# ALIMENTATION.net
KiCad netlist of a schematic drawn in EAGLE
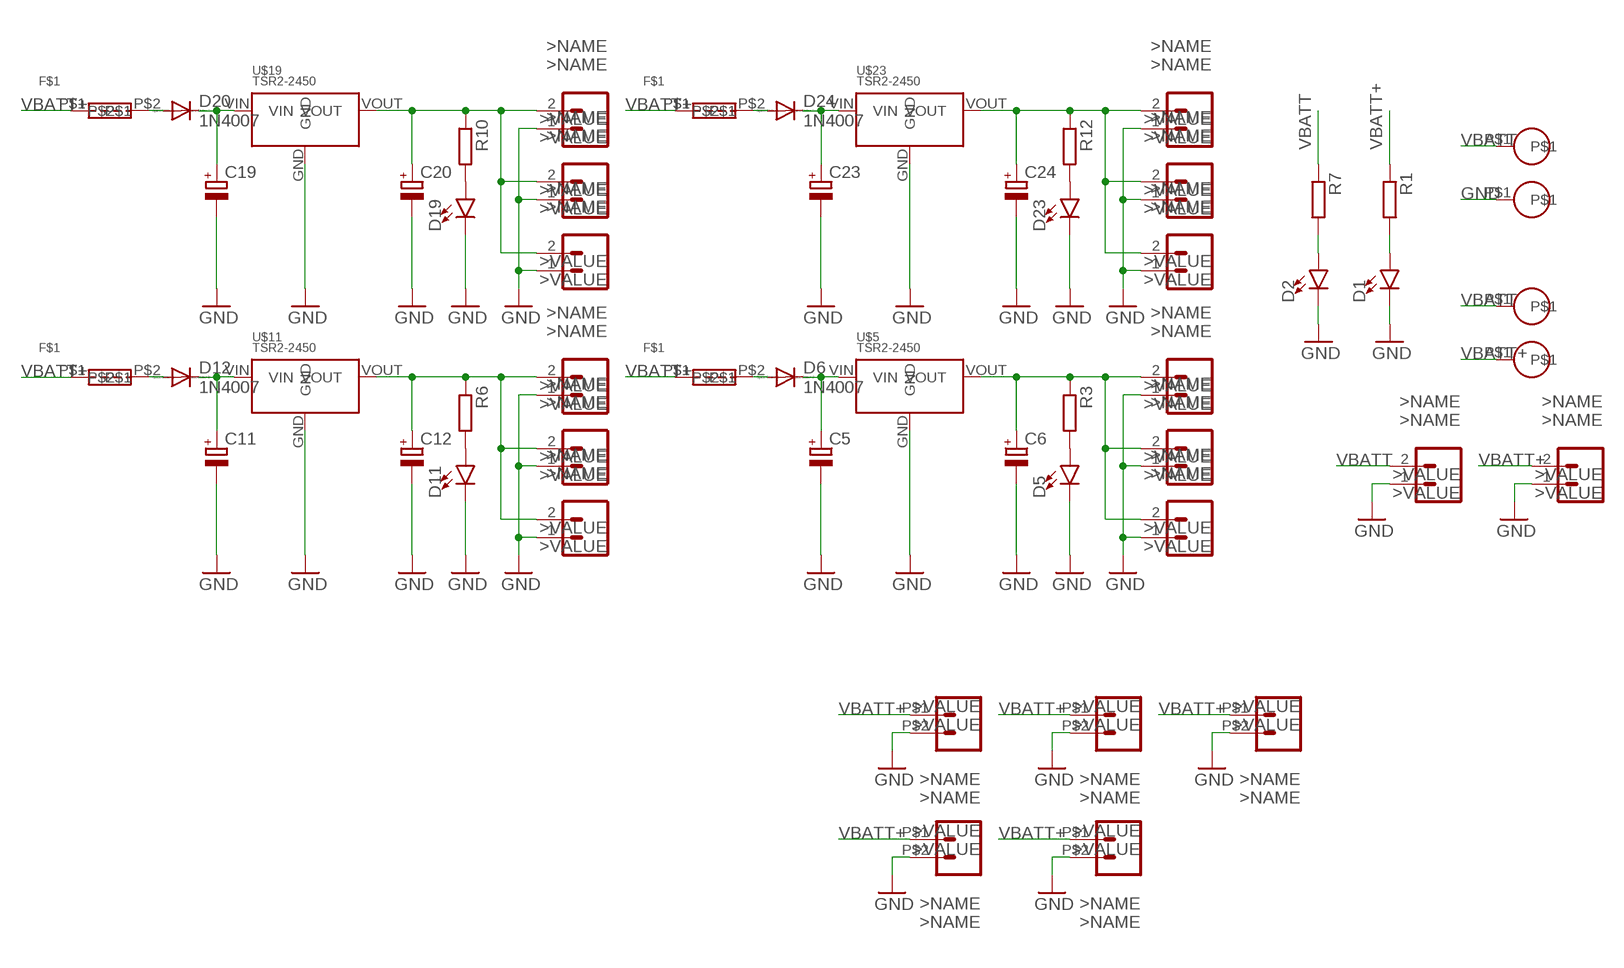
[diagram p0: schematic, sheet 1]

(export (version "E")
  (design (tool "Eeschema 10.0.6"))
  (components
    (comp (ref "C5")
      (value "CPOL-EUE2-5")
      (footprint "eagle-import:E2-5")
      (libsource (lib "eagle-import") (part "CPOL-EUE2-5"))
    )
    (comp (ref "C6")
      (value "CPOL-EUE2-5")
      (footprint "eagle-import:E2-5")
      (libsource (lib "eagle-import") (part "CPOL-EUE2-5"))
    )
    (comp (ref "C11")
      (value "CPOL-EUE2-5")
      (footprint "eagle-import:E2-5")
      (libsource (lib "eagle-import") (part "CPOL-EUE2-5"))
    )
    (comp (ref "C12")
      (value "CPOL-EUE2-5")
      (footprint "eagle-import:E2-5")
      (libsource (lib "eagle-import") (part "CPOL-EUE2-5"))
    )
    (comp (ref "C19")
      (value "CPOL-EUE2-5")
      (footprint "eagle-import:E2-5")
      (libsource (lib "eagle-import") (part "CPOL-EUE2-5"))
    )
    (comp (ref "C20")
      (value "CPOL-EUE2-5")
      (footprint "eagle-import:E2-5")
      (libsource (lib "eagle-import") (part "CPOL-EUE2-5"))
    )
    (comp (ref "C23")
      (value "CPOL-EUE2-5")
      (footprint "eagle-import:E2-5")
      (libsource (lib "eagle-import") (part "CPOL-EUE2-5"))
    )
    (comp (ref "C24")
      (value "CPOL-EUE2-5")
      (footprint "eagle-import:E2-5")
      (libsource (lib "eagle-import") (part "CPOL-EUE2-5"))
    )
    (comp (ref "D1")
      (value "LED3MM")
      (footprint "eagle-import:LED_3MM")
      (libsource (lib "eagle-import") (part "LED3MM"))
    )
    (comp (ref "D2")
      (value "LED3MM")
      (footprint "eagle-import:LED_3MM")
      (libsource (lib "eagle-import") (part "LED3MM"))
    )
    (comp (ref "D5")
      (value "LED3MM")
      (footprint "eagle-import:LED_3MM")
      (libsource (lib "eagle-import") (part "LED3MM"))
    )
    (comp (ref "D6")
      (value "1N4007")
      (footprint "eagle-import:DO41-10")
      (libsource (lib "eagle-import") (part "1N4004"))
    )
    (comp (ref "D11")
      (value "LED3MM")
      (footprint "eagle-import:LED_3MM")
      (libsource (lib "eagle-import") (part "LED3MM"))
    )
    (comp (ref "D12")
      (value "1N4007")
      (footprint "eagle-import:DO41-10")
      (libsource (lib "eagle-import") (part "1N4004"))
    )
    (comp (ref "D19")
      (value "LED3MM")
      (footprint "eagle-import:LED_3MM")
      (libsource (lib "eagle-import") (part "LED3MM"))
    )
    (comp (ref "D20")
      (value "1N4007")
      (footprint "eagle-import:DO41-10")
      (libsource (lib "eagle-import") (part "1N4004"))
    )
    (comp (ref "D23")
      (value "LED3MM")
      (footprint "eagle-import:LED_3MM")
      (libsource (lib "eagle-import") (part "LED3MM"))
    )
    (comp (ref "D24")
      (value "1N4007")
      (footprint "eagle-import:DO41-10")
      (libsource (lib "eagle-import") (part "1N4004"))
    )
    (comp (ref "J1")
      (value "CONN_02POLAR")
      (footprint "eagle-import:MOLEX-1X2")
      (libsource (lib "eagle-import") (part "CONN_02POLAR"))
    )
    (comp (ref "J2")
      (value "CONN_02POLAR")
      (footprint "eagle-import:MOLEX-1X2")
      (libsource (lib "eagle-import") (part "CONN_02POLAR"))
    )
    (comp (ref "J3")
      (value "CONN_027A-C")
      (footprint "eagle-import:NSK396-2C")
      (libsource (lib "eagle-import") (part "CONN_027A-C"))
    )
    (comp (ref "J7")
      (value "CONN_02POLAR")
      (footprint "eagle-import:MOLEX-1X2")
      (libsource (lib "eagle-import") (part "CONN_02POLAR"))
    )
    (comp (ref "J8")
      (value "CONN_02POLAR")
      (footprint "eagle-import:MOLEX-1X2")
      (libsource (lib "eagle-import") (part "CONN_02POLAR"))
    )
    (comp (ref "J9")
      (value "CONN_02POLAR")
      (footprint "eagle-import:MOLEX-1X2")
      (libsource (lib "eagle-import") (part "CONN_02POLAR"))
    )
    (comp (ref "J10")
      (value "CONN_027A-C")
      (footprint "eagle-import:NSK396-2C")
      (libsource (lib "eagle-import") (part "CONN_027A-C"))
    )
    (comp (ref "J11")
      (value "CONN_027A-C")
      (footprint "eagle-import:NSK396-2C")
      (libsource (lib "eagle-import") (part "CONN_027A-C"))
    )
    (comp (ref "J12")
      (value "CONN_027A-C")
      (footprint "eagle-import:NSK396-2C")
      (libsource (lib "eagle-import") (part "CONN_027A-C"))
    )
    (comp (ref "J13")
      (value "CONN_027A-C")
      (footprint "eagle-import:NSK396-2C")
      (libsource (lib "eagle-import") (part "CONN_027A-C"))
    )
    (comp (ref "J16")
      (value "CONN_02POLAR")
      (footprint "eagle-import:MOLEX-1X2")
      (libsource (lib "eagle-import") (part "CONN_02POLAR"))
    )
    (comp (ref "J17")
      (value "CONN_02POLAR")
      (footprint "eagle-import:MOLEX-1X2")
      (libsource (lib "eagle-import") (part "CONN_02POLAR"))
    )
    (comp (ref "J18")
      (value "CONN_02POLAR")
      (footprint "eagle-import:MOLEX-1X2")
      (libsource (lib "eagle-import") (part "CONN_02POLAR"))
    )
    (comp (ref "J28")
      (value "CONN_02POLAR")
      (footprint "eagle-import:MOLEX-1X2")
      (libsource (lib "eagle-import") (part "CONN_02POLAR"))
    )
    (comp (ref "J29")
      (value "CONN_02POLAR")
      (footprint "eagle-import:MOLEX-1X2")
      (libsource (lib "eagle-import") (part "CONN_02POLAR"))
    )
    (comp (ref "J30")
      (value "CONN_02POLAR")
      (footprint "eagle-import:MOLEX-1X2")
      (libsource (lib "eagle-import") (part "CONN_02POLAR"))
    )
    (comp (ref "J34")
      (value "CONN_02POLAR")
      (footprint "eagle-import:MOLEX-1X2")
      (libsource (lib "eagle-import") (part "CONN_02POLAR"))
    )
    (comp (ref "J35")
      (value "CONN_02POLAR")
      (footprint "eagle-import:MOLEX-1X2")
      (libsource (lib "eagle-import") (part "CONN_02POLAR"))
    )
    (comp (ref "J36")
      (value "CONN_02POLAR")
      (footprint "eagle-import:MOLEX-1X2")
      (libsource (lib "eagle-import") (part "CONN_02POLAR"))
    )
    (comp (ref "R1")
      (value "R-EU_0204/2V")
      (footprint "eagle-import:0204V")
      (libsource (lib "eagle-import") (part "R-EU_0204/2V"))
    )
    (comp (ref "R3")
      (value "R-EU_0204/2V")
      (footprint "eagle-import:0204V")
      (libsource (lib "eagle-import") (part "R-EU_0204/2V"))
    )
    (comp (ref "R6")
      (value "R-EU_0204/2V")
      (footprint "eagle-import:0204V")
      (libsource (lib "eagle-import") (part "R-EU_0204/2V"))
    )
    (comp (ref "R7")
      (value "R-EU_0204/2V")
      (footprint "eagle-import:0204V")
      (libsource (lib "eagle-import") (part "R-EU_0204/2V"))
    )
    (comp (ref "R10")
      (value "R-EU_0204/2V")
      (footprint "eagle-import:0204V")
      (libsource (lib "eagle-import") (part "R-EU_0204/2V"))
    )
    (comp (ref "R12")
      (value "R-EU_0204/2V")
      (footprint "eagle-import:0204V")
      (libsource (lib "eagle-import") (part "R-EU_0204/2V"))
    )
    (comp (ref "U$1")
      (value "BATTERY_PAD")
      (footprint "eagle-import:BATTERY_PAD")
      (libsource (lib "eagle-import") (part "BATTERY_PAD"))
    )
    (comp (ref "U$2")
      (value "BATTERY_PAD")
      (footprint "eagle-import:BATTERY_PAD")
      (libsource (lib "eagle-import") (part "BATTERY_PAD"))
    )
    (comp (ref "U$5")
      (value "TSR2-2450")
      (footprint "eagle-import:TSR2-2450")
      (libsource (lib "eagle-import") (part "TSR2-2450"))
    )
    (comp (ref "U$6")
      (value "RUEF_POLY")
      (footprint "eagle-import:RUEF185")
      (libsource (lib "eagle-import") (part "RUEF_POLY"))
    )
    (comp (ref "U$11")
      (value "TSR2-2450")
      (footprint "eagle-import:TSR2-2450")
      (libsource (lib "eagle-import") (part "TSR2-2450"))
    )
    (comp (ref "U$12")
      (value "RUEF_POLY")
      (footprint "eagle-import:RUEF185")
      (libsource (lib "eagle-import") (part "RUEF_POLY"))
    )
    (comp (ref "U$13")
      (value "BATTERY_PAD")
      (footprint "eagle-import:BATTERY_PAD")
      (libsource (lib "eagle-import") (part "BATTERY_PAD"))
    )
    (comp (ref "U$14")
      (value "BATTERY_PAD")
      (footprint "eagle-import:BATTERY_PAD")
      (libsource (lib "eagle-import") (part "BATTERY_PAD"))
    )
    (comp (ref "U$19")
      (value "TSR2-2450")
      (footprint "eagle-import:TSR2-2450")
      (libsource (lib "eagle-import") (part "TSR2-2450"))
    )
    (comp (ref "U$20")
      (value "RUEF_POLY")
      (footprint "eagle-import:RUEF185")
      (libsource (lib "eagle-import") (part "RUEF_POLY"))
    )
    (comp (ref "U$23")
      (value "TSR2-2450")
      (footprint "eagle-import:TSR2-2450")
      (libsource (lib "eagle-import") (part "TSR2-2450"))
    )
    (comp (ref "U$24")
      (value "RUEF_POLY")
      (footprint "eagle-import:RUEF185")
      (libsource (lib "eagle-import") (part "RUEF_POLY"))
    )
  )
  (nets
    (net (code "1") (name "/VBATT") (class "Default")
      (node (ref "J1") (pin "2") (pinfunction "2_2") (pintype "passive"))
      (node (ref "R7") (pin "1") (pinfunction "1_1") (pintype "passive"))
      (node (ref "U$1") (pin "P$1") (pinfunction "P$1_P$1") (pintype "bidirectional"))
      (node (ref "U$13") (pin "P$1") (pinfunction "P$1_P$1") (pintype "bidirectional"))
    )
    (net (code "2") (name "/VBATT+") (class "Default")
      (node (ref "J10") (pin "P$1") (pinfunction "1_P$1") (pintype "passive"))
      (node (ref "J11") (pin "P$1") (pinfunction "1_P$1") (pintype "passive"))
      (node (ref "J12") (pin "P$1") (pinfunction "1_P$1") (pintype "passive"))
      (node (ref "J13") (pin "P$1") (pinfunction "1_P$1") (pintype "passive"))
      (node (ref "J2") (pin "2") (pinfunction "2_2") (pintype "passive"))
      (node (ref "J3") (pin "P$1") (pinfunction "1_P$1") (pintype "passive"))
      (node (ref "R1") (pin "1") (pinfunction "1_1") (pintype "passive"))
      (node (ref "U$12") (pin "P$1") (pinfunction "P$1_P$1") (pintype "bidirectional"))
      (node (ref "U$14") (pin "P$1") (pinfunction "P$1_P$1") (pintype "bidirectional"))
      (node (ref "U$20") (pin "P$1") (pinfunction "P$1_P$1") (pintype "bidirectional"))
      (node (ref "U$24") (pin "P$1") (pinfunction "P$1_P$1") (pintype "bidirectional"))
      (node (ref "U$6") (pin "P$1") (pinfunction "P$1_P$1") (pintype "bidirectional"))
    )
    (net (code "3") (name "GND") (class "Default")
      (node (ref "C11") (pin "-") (pinfunction "-_-") (pintype "passive"))
      (node (ref "C12") (pin "-") (pinfunction "-_-") (pintype "passive"))
      (node (ref "C19") (pin "-") (pinfunction "-_-") (pintype "passive"))
      (node (ref "C20") (pin "-") (pinfunction "-_-") (pintype "passive"))
      (node (ref "C23") (pin "-") (pinfunction "-_-") (pintype "passive"))
      (node (ref "C24") (pin "-") (pinfunction "-_-") (pintype "passive"))
      (node (ref "C5") (pin "-") (pinfunction "-_-") (pintype "passive"))
      (node (ref "C6") (pin "-") (pinfunction "-_-") (pintype "passive"))
      (node (ref "D1") (pin "K") (pinfunction "C_K") (pintype "passive"))
      (node (ref "D11") (pin "K") (pinfunction "C_K") (pintype "passive"))
      (node (ref "D19") (pin "K") (pinfunction "C_K") (pintype "passive"))
      (node (ref "D2") (pin "K") (pinfunction "C_K") (pintype "passive"))
      (node (ref "D23") (pin "K") (pinfunction "C_K") (pintype "passive"))
      (node (ref "D5") (pin "K") (pinfunction "C_K") (pintype "passive"))
      (node (ref "J1") (pin "1") (pinfunction "1_1") (pintype "passive"))
      (node (ref "J10") (pin "P$2") (pinfunction "2_P$2") (pintype "passive"))
      (node (ref "J11") (pin "P$2") (pinfunction "2_P$2") (pintype "passive"))
      (node (ref "J12") (pin "P$2") (pinfunction "2_P$2") (pintype "passive"))
      (node (ref "J13") (pin "P$2") (pinfunction "2_P$2") (pintype "passive"))
      (node (ref "J16") (pin "1") (pinfunction "1_1") (pintype "passive"))
      (node (ref "J17") (pin "1") (pinfunction "1_1") (pintype "passive"))
      (node (ref "J18") (pin "1") (pinfunction "1_1") (pintype "passive"))
      (node (ref "J2") (pin "1") (pinfunction "1_1") (pintype "passive"))
      (node (ref "J28") (pin "1") (pinfunction "1_1") (pintype "passive"))
      (node (ref "J29") (pin "1") (pinfunction "1_1") (pintype "passive"))
      (node (ref "J3") (pin "P$2") (pinfunction "2_P$2") (pintype "passive"))
      (node (ref "J30") (pin "1") (pinfunction "1_1") (pintype "passive"))
      (node (ref "J34") (pin "1") (pinfunction "1_1") (pintype "passive"))
      (node (ref "J35") (pin "1") (pinfunction "1_1") (pintype "passive"))
      (node (ref "J36") (pin "1") (pinfunction "1_1") (pintype "passive"))
      (node (ref "J7") (pin "1") (pinfunction "1_1") (pintype "passive"))
      (node (ref "J8") (pin "1") (pinfunction "1_1") (pintype "passive"))
      (node (ref "J9") (pin "1") (pinfunction "1_1") (pintype "passive"))
      (node (ref "U$11") (pin "GND") (pinfunction "GND_GND") (pintype "bidirectional"))
      (node (ref "U$19") (pin "GND") (pinfunction "GND_GND") (pintype "bidirectional"))
      (node (ref "U$2") (pin "P$1") (pinfunction "P$1_P$1") (pintype "bidirectional"))
      (node (ref "U$23") (pin "GND") (pinfunction "GND_GND") (pintype "bidirectional"))
      (node (ref "U$5") (pin "GND") (pinfunction "GND_GND") (pintype "bidirectional"))
    )
    (net (code "4") (name "Net-(C5-Pad+)") (class "Default")
      (node (ref "C5") (pin "+") (pinfunction "+_+") (pintype "passive"))
      (node (ref "D6") (pin "C") (pinfunction "C_C") (pintype "passive"))
      (node (ref "U$5") (pin "VIN") (pinfunction "VIN_VIN") (pintype "bidirectional"))
    )
    (net (code "5") (name "Net-(C6-Pad+)") (class "Default")
      (node (ref "C6") (pin "+") (pinfunction "+_+") (pintype "passive"))
      (node (ref "J7") (pin "2") (pinfunction "2_2") (pintype "passive"))
      (node (ref "J8") (pin "2") (pinfunction "2_2") (pintype "passive"))
      (node (ref "J9") (pin "2") (pinfunction "2_2") (pintype "passive"))
      (node (ref "R3") (pin "1") (pinfunction "1_1") (pintype "passive"))
      (node (ref "U$5") (pin "VOUT") (pinfunction "VOUT_VOUT") (pintype "bidirectional"))
    )
    (net (code "6") (name "Net-(C11-Pad+)") (class "Default")
      (node (ref "C11") (pin "+") (pinfunction "+_+") (pintype "passive"))
      (node (ref "D12") (pin "C") (pinfunction "C_C") (pintype "passive"))
      (node (ref "U$11") (pin "VIN") (pinfunction "VIN_VIN") (pintype "bidirectional"))
    )
    (net (code "7") (name "Net-(C12-Pad+)") (class "Default")
      (node (ref "C12") (pin "+") (pinfunction "+_+") (pintype "passive"))
      (node (ref "J16") (pin "2") (pinfunction "2_2") (pintype "passive"))
      (node (ref "J17") (pin "2") (pinfunction "2_2") (pintype "passive"))
      (node (ref "J18") (pin "2") (pinfunction "2_2") (pintype "passive"))
      (node (ref "R6") (pin "1") (pinfunction "1_1") (pintype "passive"))
      (node (ref "U$11") (pin "VOUT") (pinfunction "VOUT_VOUT") (pintype "bidirectional"))
    )
    (net (code "8") (name "Net-(C19-Pad+)") (class "Default")
      (node (ref "C19") (pin "+") (pinfunction "+_+") (pintype "passive"))
      (node (ref "D20") (pin "C") (pinfunction "C_C") (pintype "passive"))
      (node (ref "U$19") (pin "VIN") (pinfunction "VIN_VIN") (pintype "bidirectional"))
    )
    (net (code "9") (name "Net-(C20-Pad+)") (class "Default")
      (node (ref "C20") (pin "+") (pinfunction "+_+") (pintype "passive"))
      (node (ref "J28") (pin "2") (pinfunction "2_2") (pintype "passive"))
      (node (ref "J29") (pin "2") (pinfunction "2_2") (pintype "passive"))
      (node (ref "J30") (pin "2") (pinfunction "2_2") (pintype "passive"))
      (node (ref "R10") (pin "1") (pinfunction "1_1") (pintype "passive"))
      (node (ref "U$19") (pin "VOUT") (pinfunction "VOUT_VOUT") (pintype "bidirectional"))
    )
    (net (code "10") (name "Net-(C23-Pad+)") (class "Default")
      (node (ref "C23") (pin "+") (pinfunction "+_+") (pintype "passive"))
      (node (ref "D24") (pin "C") (pinfunction "C_C") (pintype "passive"))
      (node (ref "U$23") (pin "VIN") (pinfunction "VIN_VIN") (pintype "bidirectional"))
    )
    (net (code "11") (name "Net-(C24-Pad+)") (class "Default")
      (node (ref "C24") (pin "+") (pinfunction "+_+") (pintype "passive"))
      (node (ref "J34") (pin "2") (pinfunction "2_2") (pintype "passive"))
      (node (ref "J35") (pin "2") (pinfunction "2_2") (pintype "passive"))
      (node (ref "J36") (pin "2") (pinfunction "2_2") (pintype "passive"))
      (node (ref "R12") (pin "1") (pinfunction "1_1") (pintype "passive"))
      (node (ref "U$23") (pin "VOUT") (pinfunction "VOUT_VOUT") (pintype "bidirectional"))
    )
    (net (code "12") (name "Net-(D1-PadA)") (class "Default")
      (node (ref "D1") (pin "A") (pinfunction "A_A") (pintype "passive"))
      (node (ref "R1") (pin "2") (pinfunction "2_2") (pintype "passive"))
    )
    (net (code "13") (name "Net-(D2-PadA)") (class "Default")
      (node (ref "D2") (pin "A") (pinfunction "A_A") (pintype "passive"))
      (node (ref "R7") (pin "2") (pinfunction "2_2") (pintype "passive"))
    )
    (net (code "14") (name "Net-(D5-PadA)") (class "Default")
      (node (ref "D5") (pin "A") (pinfunction "A_A") (pintype "passive"))
      (node (ref "R3") (pin "2") (pinfunction "2_2") (pintype "passive"))
    )
    (net (code "15") (name "Net-(D6-PadA)") (class "Default")
      (node (ref "D6") (pin "A") (pinfunction "A_A") (pintype "passive"))
      (node (ref "U$6") (pin "P$2") (pinfunction "P$2_P$2") (pintype "bidirectional"))
    )
    (net (code "16") (name "Net-(D11-PadA)") (class "Default")
      (node (ref "D11") (pin "A") (pinfunction "A_A") (pintype "passive"))
      (node (ref "R6") (pin "2") (pinfunction "2_2") (pintype "passive"))
    )
    (net (code "17") (name "Net-(D12-PadA)") (class "Default")
      (node (ref "D12") (pin "A") (pinfunction "A_A") (pintype "passive"))
      (node (ref "U$12") (pin "P$2") (pinfunction "P$2_P$2") (pintype "bidirectional"))
    )
    (net (code "18") (name "Net-(D19-PadA)") (class "Default")
      (node (ref "D19") (pin "A") (pinfunction "A_A") (pintype "passive"))
      (node (ref "R10") (pin "2") (pinfunction "2_2") (pintype "passive"))
    )
    (net (code "19") (name "Net-(D20-PadA)") (class "Default")
      (node (ref "D20") (pin "A") (pinfunction "A_A") (pintype "passive"))
      (node (ref "U$20") (pin "P$2") (pinfunction "P$2_P$2") (pintype "bidirectional"))
    )
    (net (code "20") (name "Net-(D23-PadA)") (class "Default")
      (node (ref "D23") (pin "A") (pinfunction "A_A") (pintype "passive"))
      (node (ref "R12") (pin "2") (pinfunction "2_2") (pintype "passive"))
    )
    (net (code "21") (name "Net-(D24-PadA)") (class "Default")
      (node (ref "D24") (pin "A") (pinfunction "A_A") (pintype "passive"))
      (node (ref "U$24") (pin "P$2") (pinfunction "P$2_P$2") (pintype "bidirectional"))
    )
  )
)
